# job17.net
KiCad netlist of a schematic drawn in EAGLE
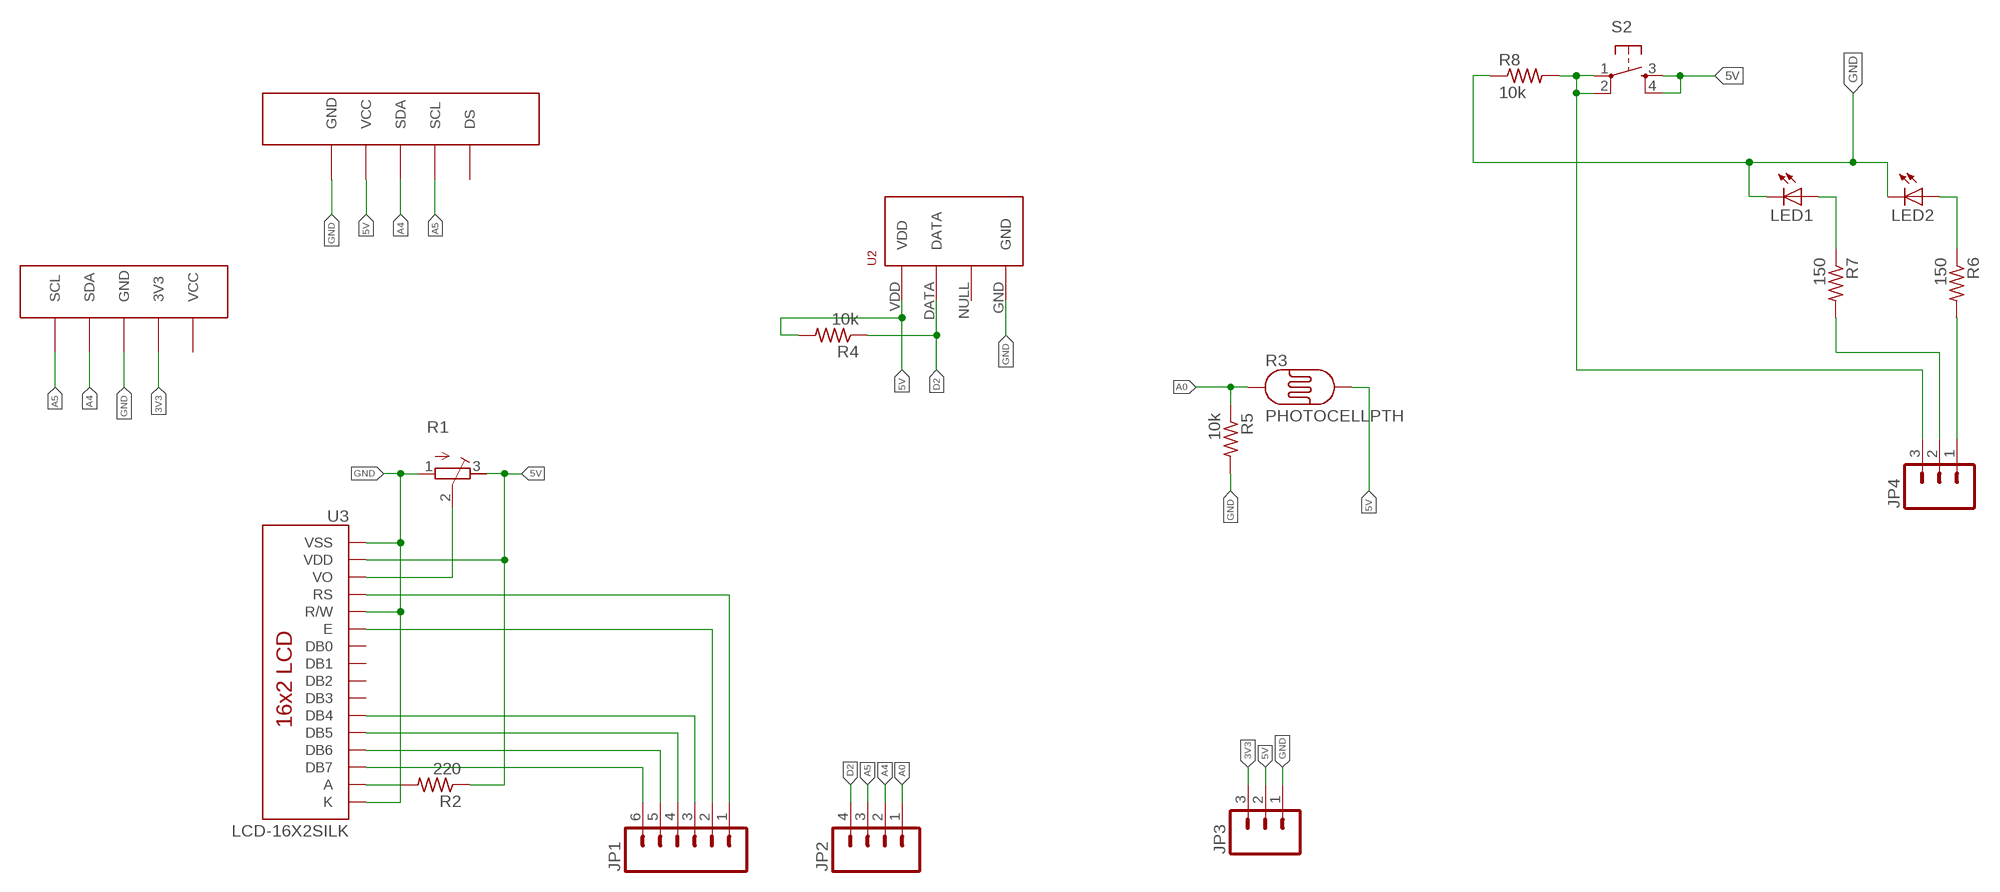
[diagram p0: schematic, sheet 1]

(export (version "E")
  (design (tool "Eeschema 10.0.6"))
  (components
    (comp (ref "JP1")
      (value "M06SIP")
      (footprint "eagle-import:1X06")
      (libsource (lib "eagle-import") (part "M06SIP"))
    )
    (comp (ref "JP2")
      (value "M04PTH")
      (footprint "eagle-import:1X04")
      (libsource (lib "eagle-import") (part "M04PTH"))
    )
    (comp (ref "JP3")
      (value "M03PTH")
      (footprint "eagle-import:1X03")
      (libsource (lib "eagle-import") (part "M03PTH"))
    )
    (comp (ref "JP4")
      (value "M03PTH")
      (footprint "eagle-import:1X03")
      (libsource (lib "eagle-import") (part "M03PTH"))
    )
    (comp (ref "LED1")
      (value "LED5MM")
      (footprint "eagle-import:LED5MM")
      (libsource (lib "eagle-import") (part "LED5MM"))
    )
    (comp (ref "LED2")
      (value "LED5MM")
      (footprint "eagle-import:LED5MM")
      (libsource (lib "eagle-import") (part "LED5MM"))
    )
    (comp (ref "R1")
      (value "R-TRIMM3339P")
      (footprint "eagle-import:RTRIM3339P")
      (libsource (lib "eagle-import") (part "R-TRIMM3339P"))
    )
    (comp (ref "R2")
      (value "220")
      (footprint "eagle-import:0207_10")
      (libsource (lib "eagle-import") (part "R-US_0207/10"))
    )
    (comp (ref "R3")
      (value "PHOTOCELLPTH")
      (footprint "eagle-import:PHOTOCELL")
      (libsource (lib "eagle-import") (part "PHOTOCELLPTH"))
    )
    (comp (ref "R4")
      (value "10k")
      (footprint "eagle-import:0207_10")
      (libsource (lib "eagle-import") (part "R-US_0207/10"))
    )
    (comp (ref "R5")
      (value "10k")
      (footprint "eagle-import:0207_10")
      (libsource (lib "eagle-import") (part "R-US_0207/10"))
    )
    (comp (ref "R6")
      (value "150")
      (footprint "eagle-import:0207_10")
      (libsource (lib "eagle-import") (part "R-US_0207/10"))
    )
    (comp (ref "R7")
      (value "150")
      (footprint "eagle-import:0207_10")
      (libsource (lib "eagle-import") (part "R-US_0207/10"))
    )
    (comp (ref "R8")
      (value "10k")
      (footprint "eagle-import:0207_10")
      (libsource (lib "eagle-import") (part "R-US_0207/10"))
    )
    (comp (ref "RTC1")
      (value "TINY_RTC")
      (footprint "eagle-import:TINY_RTC")
      (libsource (lib "eagle-import") (part "TINY_RTC"))
    )
    (comp (ref "S1")
      (value "BMP085")
      (footprint "eagle-import:BMP085")
      (libsource (lib "eagle-import") (part "BMP085"))
    )
    (comp (ref "S2")
      (value "TAC_SWITCHPTH")
      (footprint "eagle-import:TACTILE-PTH")
      (libsource (lib "eagle-import") (part "TAC_SWITCHPTH"))
    )
    (comp (ref "U2")
      (value "RHT03_DHT-22_AM2302RA")
      (footprint "eagle-import:RHT03_DHT-22_RA")
      (libsource (lib "eagle-import") (part "RHT03_DHT-22_AM2302RA"))
    )
    (comp (ref "U3")
      (value "LCD-16X2SILK")
      (footprint "eagle-import:LCD-16X2")
      (libsource (lib "eagle-import") (part "LCD-16X2SILK"))
    )
  )
  (nets
    (net (code "1") (name "3V3") (class "Default")
      (node (ref "JP3") (pin "3") (pinfunction "3_3") (pintype "passive"))
      (node (ref "S1") (pin "3V3") (pinfunction "3V3_3V3") (pintype "bidirectional"))
    )
    (net (code "2") (name "5V") (class "Default")
      (node (ref "JP3") (pin "2") (pinfunction "2_2") (pintype "passive"))
      (node (ref "R1") (pin "3") (pinfunction "E_3") (pintype "passive"))
      (node (ref "R2") (pin "1") (pinfunction "1_1") (pintype "passive"))
      (node (ref "R3") (pin "2") (pinfunction "P$2_2") (pintype "bidirectional"))
      (node (ref "R4") (pin "2") (pinfunction "2_2") (pintype "passive"))
      (node (ref "RTC1") (pin "VCC") (pinfunction "VCC_VCC") (pintype "bidirectional"))
      (node (ref "S2") (pin "3") (pinfunction "3_3") (pintype "passive"))
      (node (ref "S2") (pin "4") (pinfunction "4_4") (pintype "passive"))
      (node (ref "U2") (pin "VDD") (pinfunction "VDD_VDD") (pintype "power_in"))
      (node (ref "U3") (pin "2") (pinfunction "VDD_2") (pintype "power_in"))
    )
    (net (code "3") (name "A0") (class "Default")
      (node (ref "JP2") (pin "1") (pinfunction "1_1") (pintype "passive"))
      (node (ref "R3") (pin "1") (pinfunction "P$1_1") (pintype "bidirectional"))
      (node (ref "R5") (pin "1") (pinfunction "1_1") (pintype "passive"))
    )
    (net (code "4") (name "A4") (class "Default")
      (node (ref "JP2") (pin "2") (pinfunction "2_2") (pintype "passive"))
      (node (ref "RTC1") (pin "SDA") (pinfunction "SDA_SDA") (pintype "bidirectional"))
      (node (ref "S1") (pin "SDA") (pinfunction "SDA_SDA") (pintype "bidirectional"))
    )
    (net (code "5") (name "A5") (class "Default")
      (node (ref "JP2") (pin "3") (pinfunction "3_3") (pintype "passive"))
      (node (ref "RTC1") (pin "SCL") (pinfunction "SCL_SCL") (pintype "bidirectional"))
      (node (ref "S1") (pin "SCL") (pinfunction "SCL_SCL") (pintype "bidirectional"))
    )
    (net (code "6") (name "D2") (class "Default")
      (node (ref "JP2") (pin "4") (pinfunction "4_4") (pintype "passive"))
      (node (ref "R4") (pin "1") (pinfunction "1_1") (pintype "passive"))
      (node (ref "U2") (pin "DATA") (pinfunction "DATA_DATA") (pintype "bidirectional"))
    )
    (net (code "7") (name "GND") (class "Default")
      (node (ref "JP3") (pin "1") (pinfunction "1_1") (pintype "passive"))
      (node (ref "LED1") (pin "K") (pinfunction "C_K") (pintype "passive"))
      (node (ref "LED2") (pin "K") (pinfunction "C_K") (pintype "passive"))
      (node (ref "R1") (pin "1") (pinfunction "A_1") (pintype "passive"))
      (node (ref "R5") (pin "2") (pinfunction "2_2") (pintype "passive"))
      (node (ref "R8") (pin "1") (pinfunction "1_1") (pintype "passive"))
      (node (ref "RTC1") (pin "GND") (pinfunction "GND_GND") (pintype "bidirectional"))
      (node (ref "S1") (pin "GND") (pinfunction "GND_GND") (pintype "bidirectional"))
      (node (ref "U2") (pin "GND") (pinfunction "GND_GND") (pintype "power_in"))
      (node (ref "U3") (pin "1") (pinfunction "VSS_1") (pintype "power_in"))
      (node (ref "U3") (pin "16") (pinfunction "K_16") (pintype "power_in"))
      (node (ref "U3") (pin "5") (pinfunction "R/W_5") (pintype "input"))
    )
    (net (code "8") (name "Net-(JP4-Pad1)") (class "Default")
      (node (ref "JP4") (pin "1") (pinfunction "1_1") (pintype "passive"))
      (node (ref "R6") (pin "2") (pinfunction "2_2") (pintype "passive"))
    )
    (net (code "9") (name "Net-(JP4-Pad2)") (class "Default")
      (node (ref "JP4") (pin "2") (pinfunction "2_2") (pintype "passive"))
      (node (ref "R7") (pin "2") (pinfunction "2_2") (pintype "passive"))
    )
    (net (code "10") (name "Net-(JP4-Pad3)") (class "Default")
      (node (ref "JP4") (pin "3") (pinfunction "3_3") (pintype "passive"))
      (node (ref "R8") (pin "2") (pinfunction "2_2") (pintype "passive"))
      (node (ref "S2") (pin "1") (pinfunction "1_1") (pintype "passive"))
      (node (ref "S2") (pin "2") (pinfunction "2_2") (pintype "passive"))
    )
    (net (code "11") (name "Net-(LED1-PadA)") (class "Default")
      (node (ref "LED1") (pin "A") (pinfunction "A_A") (pintype "passive"))
      (node (ref "R7") (pin "1") (pinfunction "1_1") (pintype "passive"))
    )
    (net (code "12") (name "Net-(LED2-PadA)") (class "Default")
      (node (ref "LED2") (pin "A") (pinfunction "A_A") (pintype "passive"))
      (node (ref "R6") (pin "1") (pinfunction "1_1") (pintype "passive"))
    )
    (net (code "13") (name "Net-(R1-S)") (class "Default")
      (node (ref "R1") (pin "2") (pinfunction "S_2") (pintype "passive"))
      (node (ref "U3") (pin "3") (pinfunction "VO_3") (pintype "bidirectional"))
    )
    (net (code "14") (name "Net-(U3-A)") (class "Default")
      (node (ref "R2") (pin "2") (pinfunction "2_2") (pintype "passive"))
      (node (ref "U3") (pin "15") (pinfunction "A_15") (pintype "power_in"))
    )
    (net (code "15") (name "Net-(U3-DB4)") (class "Default")
      (node (ref "JP1") (pin "3") (pinfunction "3_3") (pintype "passive"))
      (node (ref "U3") (pin "11") (pinfunction "DB4_11") (pintype "bidirectional"))
    )
    (net (code "16") (name "Net-(U3-DB5)") (class "Default")
      (node (ref "JP1") (pin "4") (pinfunction "4_4") (pintype "passive"))
      (node (ref "U3") (pin "12") (pinfunction "DB5_12") (pintype "bidirectional"))
    )
    (net (code "17") (name "Net-(U3-DB6)") (class "Default")
      (node (ref "JP1") (pin "5") (pinfunction "5_5") (pintype "passive"))
      (node (ref "U3") (pin "13") (pinfunction "DB6_13") (pintype "bidirectional"))
    )
    (net (code "18") (name "Net-(U3-DB7)") (class "Default")
      (node (ref "JP1") (pin "6") (pinfunction "6_6") (pintype "passive"))
      (node (ref "U3") (pin "14") (pinfunction "DB7_14") (pintype "bidirectional"))
    )
    (net (code "19") (name "Net-(U3-E)") (class "Default")
      (node (ref "JP1") (pin "2") (pinfunction "2_2") (pintype "passive"))
      (node (ref "U3") (pin "6") (pinfunction "E_6") (pintype "input"))
    )
    (net (code "20") (name "Net-(U3-RS)") (class "Default")
      (node (ref "JP1") (pin "1") (pinfunction "1_1") (pintype "passive"))
      (node (ref "U3") (pin "4") (pinfunction "RS_4") (pintype "input"))
    )
    (net (code "21") (name "unconnected-(RTC1-PadDS)") (class "Default")
      (node (ref "RTC1") (pin "DS") (pinfunction "DS_DS") (pintype "bidirectional"))
    )
    (net (code "22") (name "unconnected-(S1-PadVCC)") (class "Default")
      (node (ref "S1") (pin "VCC") (pinfunction "VCC_VCC") (pintype "bidirectional"))
    )
    (net (code "23") (name "unconnected-(U2-PadNULL)") (class "Default")
      (node (ref "U2") (pin "NULL") (pinfunction "NULL_NULL") (pintype "no_connect"))
    )
    (net (code "24") (name "unconnected-(U3-DB0-Pad7)") (class "Default")
      (node (ref "U3") (pin "7") (pinfunction "DB0_7") (pintype "bidirectional"))
    )
    (net (code "25") (name "unconnected-(U3-DB1-Pad8)") (class "Default")
      (node (ref "U3") (pin "8") (pinfunction "DB1_8") (pintype "bidirectional"))
    )
    (net (code "26") (name "unconnected-(U3-DB2-Pad9)") (class "Default")
      (node (ref "U3") (pin "9") (pinfunction "DB2_9") (pintype "bidirectional"))
    )
    (net (code "27") (name "unconnected-(U3-DB3-Pad10)") (class "Default")
      (node (ref "U3") (pin "10") (pinfunction "DB3_10") (pintype "bidirectional"))
    )
  )
)
